# sema_2.net
KiCad netlist of a schematic drawn in Altium Designer
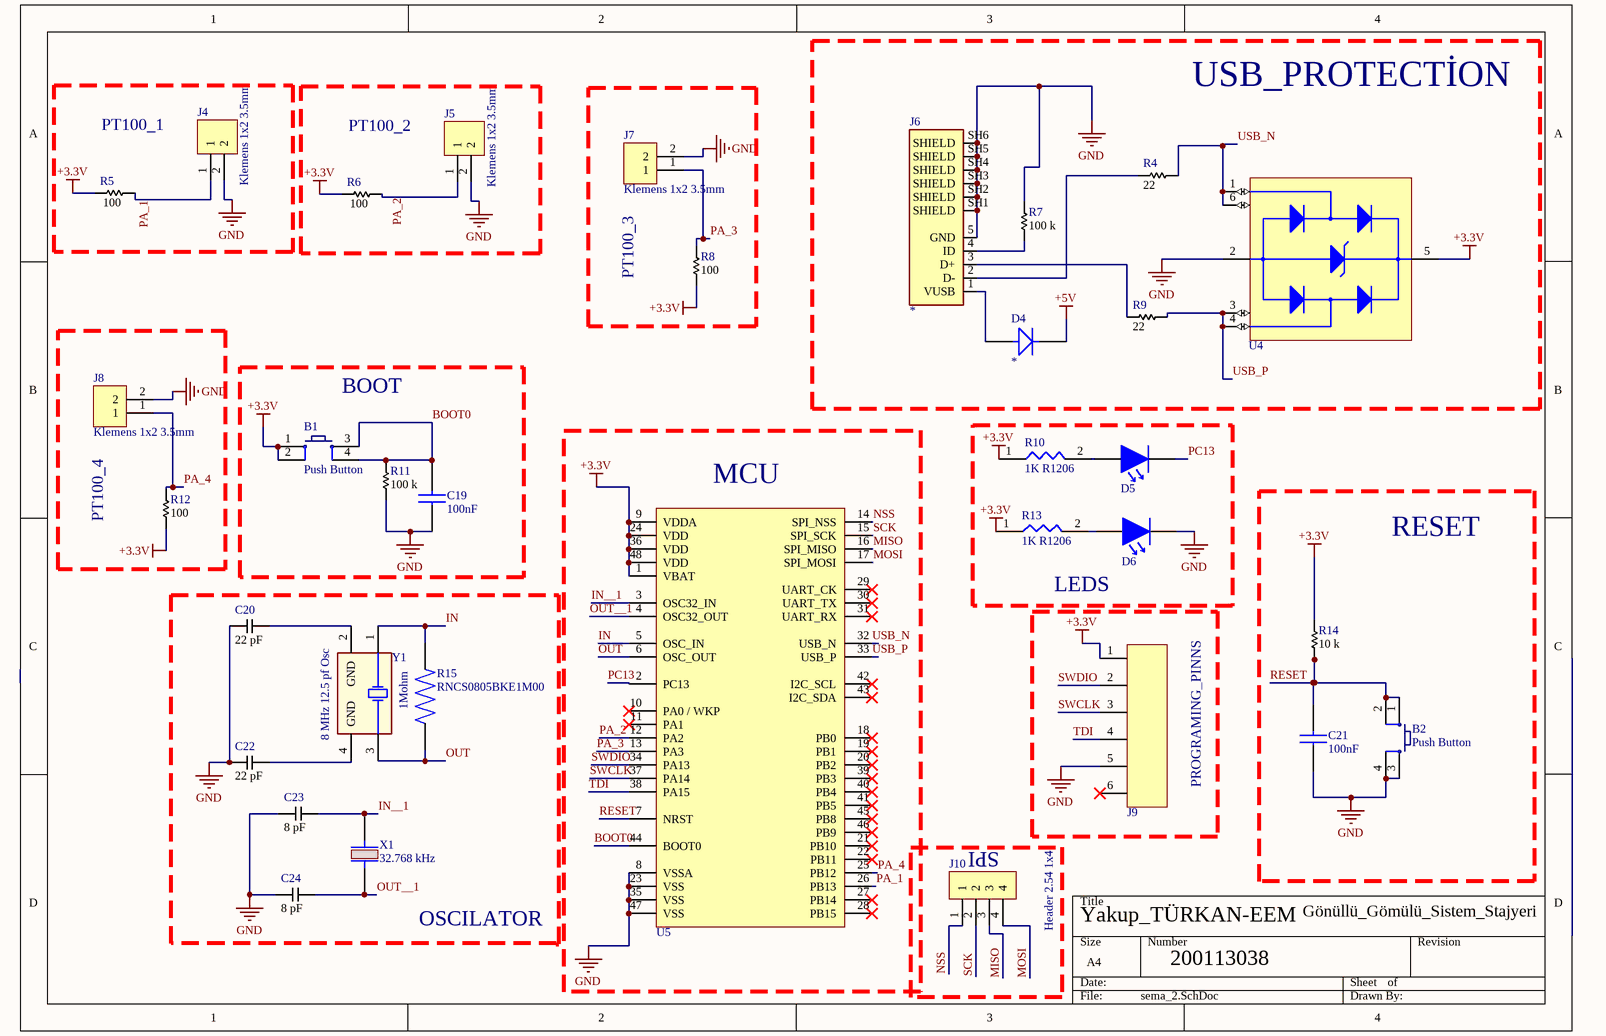
[diagram p0: sema_2.SchDoc]

(export (version "E")
  (design (tool "Eeschema 10.0.6"))
  (components
    (comp (ref "B1")
      (value "Push Button")
      (footprint "PUSB BUTTON-SMD")
      (description "Smd Push Button")
      (libsource (lib "YakupTrkn") (part "Push Button"))
    )
    (comp (ref "B2")
      (value "Push Button")
      (footprint "PUSB BUTTON-SMD")
      (description "Smd Push Button")
      (libsource (lib "YakupTrkn") (part "Push Button"))
    )
    (comp (ref "C19")
      (value "C0603C104K5RACTU")
      (footprint "CAP_0603")
      (description "CAP CER 100nF %10 0603 SMD")
      (fields
        (field (name "MANUFACTURER") "KEMET")
        (field (name "TOLERANCE") "10%")
        (field (name "CAPACITANCE") "100nF")
        (field (name "DESIGNED BY") "BERK")
      )
      (libsource (lib "YakupTrkn") (part "CAP CER 100nF 0603"))
    )
    (comp (ref "C20")
      (value "22pF")
      (footprint "SAMSUNG_CAP_0805_075")
      (description "CAP CER 27PF 50V C0G/NP0 0805")
      (fields (field (name "CAPACITANCE") "22 pF"))
      (libsource (lib "ilk") (part "22pF"))
    )
    (comp (ref "C21")
      (value "C0603C104K5RACTU")
      (footprint "CAP_0603")
      (description "CAP CER 100nF %10 0603 SMD")
      (fields
        (field (name "MANUFACTURER") "KEMET")
        (field (name "TOLERANCE") "10%")
        (field (name "CAPACITANCE") "100nF")
        (field (name "DESIGNED BY") "BERK")
      )
      (libsource (lib "YakupTrkn") (part "CAP CER 100nF 0603"))
    )
    (comp (ref "C22")
      (value "22pF")
      (footprint "SAMSUNG_CAP_0805_075")
      (description "CAP CER 27PF 50V C0G/NP0 0805")
      (fields (field (name "CAPACITANCE") "22 pF"))
      (libsource (lib "ilk") (part "22pF"))
    )
    (comp (ref "C23")
      (value "8pF")
      (footprint "SAMSUNG_CAP_0805_075")
      (description "CAP CER 1.2PF 50V C0G/NP0 0805")
      (fields (field (name "CAPACITANCE") "8 pF"))
      (libsource (lib "ilk") (part "8pF"))
    )
    (comp (ref "C24")
      (value "8pF")
      (footprint "SAMSUNG_CAP_0805_075")
      (description "CAP CER 1.2PF 50V C0G/NP0 0805")
      (fields (field (name "CAPACITANCE") "8 pF"))
      (libsource (lib "ilk") (part "8pF"))
    )
    (comp (ref "D4")
      (value "*")
      (footprint "MBRA210LT3G:DIOM5226X220N")
      (description "...employing the Schottky Barrier principle in a metal to silicon power rectifier.")
      (fields (field (name "MF") "{'manufacturer': u'ON Semiconductor'}") (field (name "MP") "MBRA210LT3G"))
      (libsource (lib "*") (part "MBRA210LT3G"))
    )
    (comp (ref "D5")
      (value "LTST-C171GKT")
      (footprint "LED_GREEN_0805")
      (description "Green 0805 130 º Min 5 mcd Typical 12 mcd Water Clear Lens SMT LED")
      (fields (field (name "MANUFACTURER") "Vishay Lite-On") (field (name "DESIGNED BY") "BERK"))
      (libsource (lib "ilk") (part "LED GREEN 0805"))
    )
    (comp (ref "D6")
      (value "LH R974-LP-1")
      (footprint "LED_RED_0805")
      (description "LED Uni-Color Hyper Red 660nm 2-Pin Chip 0805(2012Metric) T/R")
      (fields (field (name "MANUFACTURER") "Osram Opto") (field (name "DESIGNED BY") "BERK"))
      (libsource (lib "ilk") (part "LED RED 0805"))
    )
    (comp (ref "J4")
      (value "Klemens 1x2 3.5mm")
      (footprint "Klemens 1x2 - 3.5mm")
      (libsource (lib "") (part "Klemens 1x2 3.5mm_1"))
    )
    (comp (ref "J5")
      (value "Klemens 1x2 3.5mm")
      (footprint "Klemens 1x2 - 3.5mm")
      (libsource (lib "") (part "Klemens 1x2 3.5mm_1"))
    )
    (comp (ref "J6")
      (value "*")
      (footprint "10118192-0001LF:AMPHENOL_10118192-0001LF")
      (description "Single Port 5 Contact Horizontal Right Angle Shielded Micro B USB 2.0 Connector")
      (fields (field (name "MP") "10118192-0001LF") (field (name "MF") "{'manufacturer': u'FCI'}"))
      (libsource (lib "*") (part "10118192-0001LF"))
    )
    (comp (ref "J7")
      (value "Klemens 1x2 3.5mm")
      (footprint "Klemens 1x2 - 3.5mm")
      (libsource (lib "ilk") (part "Klemens 1x2 3.5mm"))
    )
    (comp (ref "J8")
      (value "Klemens 1x2 3.5mm")
      (footprint "Klemens 1x2 - 3.5mm")
      (libsource (lib "ilk") (part "Klemens 1x2 3.5mm"))
    )
    (comp (ref "J9")
      (value "64800611622")
      (footprint "64800611622")
      (description "1.50mm 6PIN Connector")
      (fields (field (name "MANUFACTURER") "Wurth Electronics"))
      (libsource (lib "*") (part "64800611622_conn_6pin"))
    )
    (comp (ref "J10")
      (value "Header 2.54 1x4")
      (footprint "Header 2.54 1x4")
      (libsource (lib "ilk") (part "Header 2.54 1x4"))
    )
    (comp (ref "R4")
      (value "0805W8J0220T5E")
      (footprint "ROYALOHM_RES_0805")
      (description "RES SMD 22 OHM 5% 1/8W 0805")
      (fields (field (name "RESISTANCE") "22"))
      (libsource (lib "YakupTrkn") (part "0805W8J0220T5E"))
    )
    (comp (ref "R5")
      (value "100ohm")
      (footprint "ROYALOHM_RES_0603")
      (description "RES SMD 100 OHM 5% 1/10W 0603")
      (fields (field (name "RESISTANCE") "100"))
      (libsource (lib "ilk") (part "100ohm"))
    )
    (comp (ref "R6")
      (value "100ohm")
      (footprint "ROYALOHM_RES_0603")
      (description "RES SMD 100 OHM 5% 1/10W 0603")
      (fields (field (name "RESISTANCE") "100"))
      (libsource (lib "ilk") (part "100ohm"))
    )
    (comp (ref "R7")
      (value "0603SAJ0104T5E")
      (footprint "ROYALOHM_RES_0603")
      (description "RES SMD 100K OHM 5% 1/10W 0603")
      (fields (field (name "RESISTANCE") "100 k"))
      (libsource (lib "YakupTrkn") (part "0603SAJ0104T5E"))
    )
    (comp (ref "R8")
      (value "100ohm")
      (footprint "ROYALOHM_RES_0603")
      (description "RES SMD 100 OHM 5% 1/10W 0603")
      (fields (field (name "RESISTANCE") "100"))
      (libsource (lib "ilk") (part "100ohm"))
    )
    (comp (ref "R9")
      (value "0805W8J0220T5E")
      (footprint "ROYALOHM_RES_0805")
      (description "RES SMD 22 OHM 5% 1/8W 0805")
      (fields (field (name "RESISTANCE") "22"))
      (libsource (lib "YakupTrkn") (part "0805W8J0220T5E"))
    )
    (comp (ref "R10")
      (value "1K R1206")
      (footprint "R1206 Resıstor")
      (libsource (lib "ilk") (part "1K R1206"))
    )
    (comp (ref "R11")
      (value "0805S8J0104T5E")
      (footprint "ROYALOHM_RES_0805")
      (description "RES SMD 100K OHM 5% 1/8W 0805")
      (fields (field (name "RESISTANCE") "100 k"))
      (libsource (lib "ilk") (part "0805S8J0104T5E"))
    )
    (comp (ref "R12")
      (value "100ohm")
      (footprint "ROYALOHM_RES_0603")
      (description "RES SMD 100 OHM 5% 1/10W 0603")
      (fields (field (name "RESISTANCE") "100"))
      (libsource (lib "ilk") (part "100ohm"))
    )
    (comp (ref "R13")
      (value "1K R1206")
      (footprint "R1206 Resıstor")
      (libsource (lib "ilk") (part "1K R1206"))
    )
    (comp (ref "R14")
      (value "10k")
      (footprint "ROYALOHM_RES_0805")
      (description "RES SMD 10K OHM 1% 1/8W 0805")
      (fields (field (name "RESISTANCE") "10 k"))
      (libsource (lib "ilk") (part "10k"))
    )
    (comp (ref "R15")
      (value "RNCS0805BKE1M00")
      (footprint "RNCS0805BKE1M00:RESC2012X65N")
      (fields (field (name "MF") "{'manufacturer': u'Stackpole Electronics Inc'}"))
      (libsource (lib "ilk") (part "RNCS0805BKE1M00"))
    )
    (comp (ref "U4")
      (value "USBLC6-2SC6")
      (footprint "SOT23-6L")
      (description "TVS DIODE 5.25V 17V SOT23-6")
      (fields (field (name "MANUFACTURER") "STMicroelectronics") (field (name "DESIGNED BY") "BERK"))
      (libsource (lib "YakupTrkn") (part "USB PROTECTION"))
    )
    (comp (ref "U5")
      (value "STM32F103C6T6A")
      (footprint "LQFP-48")
      (description "MCU 32-bit STM32F ARM Cortex M3 RISC 32KB Flash 2.5V/3.3V 48-Pin LQFP Tray")
      (fields (field (name "MANUFACTURER") "STMicroelectronics") (field (name "DESIGNED BY") "BERK"))
      (libsource (lib "ilk") (part "STM32F103C6T6A"))
    )
    (comp (ref "X1")
      (value "ABS05-32.768KHZ-T")
      (footprint "ABS05")
      (description "Crystal, 32.768 kHz, SMD, 1.6mm x 1mm, 12.5 pF, 20 ppm, ABS05 Series")
      (fields
        (field (name "MANUFACTURER") "Abracon")
        (field (name "TOLERANCE") "20ppm")
        (field (name "OPERATING FREQUENCY") "32.768 kHz")
        (field (name "DESIGNED BY") "BERK")
      )
      (libsource (lib "ilk") (part "CRYSTAL 32768kHZ"))
    )
    (comp (ref "Y1")
      (value "8 MHz 12.5 pf Osc")
      (footprint "8 MHZ Osc.")
      (libsource (lib "ilk") (part "8 MHz 12.5 pf Osc"))
    )
  )
  (nets
    (net (code "1") (name "+3.3V") (class "Default")
      (node (ref "B1") (pin "1") (pinfunction "1_1") (pintype "passive"))
      (node (ref "B1") (pin "2") (pinfunction "2_2") (pintype "passive"))
      (node (ref "J9") (pin "1") (pintype "power_in"))
      (node (ref "R10") (pin "1") (pinfunction "1_1") (pintype "passive"))
      (node (ref "R12") (pin "1") (pinfunction "1_1") (pintype "passive"))
      (node (ref "R13") (pin "1") (pinfunction "1_1") (pintype "passive"))
      (node (ref "R14") (pin "2") (pinfunction "2_2") (pintype "passive"))
      (node (ref "R5") (pin "1") (pinfunction "1_1") (pintype "passive"))
      (node (ref "R6") (pin "1") (pinfunction "1_1") (pintype "passive"))
      (node (ref "R8") (pin "1") (pinfunction "1_1") (pintype "passive"))
      (node (ref "U4") (pin "5") (pinfunction "VBUS_5") (pintype "power_in"))
      (node (ref "U5") (pin "1") (pinfunction "VBAT_1") (pintype "passive"))
      (node (ref "U5") (pin "24") (pinfunction "VDD_24") (pintype "passive"))
      (node (ref "U5") (pin "36") (pinfunction "VDD_36") (pintype "passive"))
      (node (ref "U5") (pin "48") (pinfunction "VDD_48") (pintype "passive"))
      (node (ref "U5") (pin "9") (pinfunction "VDDA_9") (pintype "passive"))
    )
    (net (code "2") (name "+5V") (class "Default")
      (node (ref "D4") (pin "1") (pinfunction "K_1") (pintype "passive"))
    )
    (net (code "3") (name "/BOOT0") (class "Default")
      (node (ref "B1") (pin "3") (pinfunction "3_3") (pintype "passive"))
      (node (ref "B1") (pin "4") (pinfunction "4_4") (pintype "passive"))
      (node (ref "C19") (pin "2") (pinfunction "2_2") (pintype "passive"))
      (node (ref "R11") (pin "2") (pinfunction "2_2") (pintype "passive"))
      (node (ref "U5") (pin "44") (pinfunction "BOOT0_44") (pintype "passive"))
    )
    (net (code "4") (name "/IN") (class "Default")
      (node (ref "R15") (pin "2") (pinfunction "2_2") (pintype "passive"))
      (node (ref "U5") (pin "5") (pinfunction "OSC_IN_5") (pintype "passive"))
      (node (ref "Y1") (pin "1") (pintype "power_in"))
    )
    (net (code "5") (name "/IN__1") (class "Default")
      (node (ref "C23") (pin "2") (pinfunction "2_2") (pintype "passive"))
      (node (ref "U5") (pin "3") (pinfunction "OSC32_IN_3") (pintype "passive"))
      (node (ref "X1") (pin "2") (pinfunction "2_2") (pintype "passive"))
    )
    (net (code "6") (name "/MISO") (class "Default")
      (node (ref "J10") (pin "3") (pinfunction "3_3") (pintype "passive"))
      (node (ref "U5") (pin "16") (pinfunction "SPI_MISO_16") (pintype "passive"))
    )
    (net (code "7") (name "/MOSI") (class "Default")
      (node (ref "J10") (pin "4") (pinfunction "4_4") (pintype "passive"))
      (node (ref "U5") (pin "17") (pinfunction "SPI_MOSI_17") (pintype "passive"))
    )
    (net (code "8") (name "/NSS") (class "Default")
      (node (ref "J10") (pin "1") (pinfunction "1_1") (pintype "passive"))
      (node (ref "U5") (pin "14") (pinfunction "SPI_NSS_14") (pintype "passive"))
    )
    (net (code "9") (name "/OUT") (class "Default")
      (node (ref "R15") (pin "1") (pinfunction "1_1") (pintype "passive"))
      (node (ref "U5") (pin "6") (pinfunction "OSC_OUT_6") (pintype "passive"))
      (node (ref "Y1") (pin "3") (pintype "passive"))
    )
    (net (code "10") (name "/OUT__1") (class "Default")
      (node (ref "C24") (pin "2") (pinfunction "2_2") (pintype "passive"))
      (node (ref "U5") (pin "4") (pinfunction "OSC32_OUT_4") (pintype "passive"))
      (node (ref "X1") (pin "1") (pinfunction "1_1") (pintype "passive"))
    )
    (net (code "11") (name "/PA_1") (class "Default")
      (node (ref "J4") (pin "1") (pinfunction "1_1") (pintype "passive"))
      (node (ref "R5") (pin "2") (pinfunction "2_2") (pintype "passive"))
      (node (ref "U5") (pin "26") (pinfunction "PB13_26") (pintype "passive"))
    )
    (net (code "12") (name "/PA_2") (class "Default")
      (node (ref "J5") (pin "1") (pinfunction "1_1") (pintype "passive"))
      (node (ref "R6") (pin "2") (pinfunction "2_2") (pintype "passive"))
      (node (ref "U5") (pin "12") (pinfunction "PA2_12") (pintype "passive"))
    )
    (net (code "13") (name "/PA_3") (class "Default")
      (node (ref "J7") (pin "1") (pinfunction "1_1") (pintype "passive"))
      (node (ref "R8") (pin "2") (pinfunction "2_2") (pintype "passive"))
      (node (ref "U5") (pin "13") (pinfunction "PA3_13") (pintype "passive"))
    )
    (net (code "14") (name "/PA_4") (class "Default")
      (node (ref "J8") (pin "1") (pinfunction "1_1") (pintype "passive"))
      (node (ref "R12") (pin "2") (pinfunction "2_2") (pintype "passive"))
      (node (ref "U5") (pin "25") (pinfunction "PB12_25") (pintype "passive"))
    )
    (net (code "15") (name "/PC13") (class "Default")
      (node (ref "D5") (pin "1") (pinfunction "1_1") (pintype "power_in"))
      (node (ref "U5") (pin "2") (pinfunction "PC13_2") (pintype "passive"))
    )
    (net (code "16") (name "/RESET") (class "Default")
      (node (ref "B2") (pin "1") (pinfunction "1_1") (pintype "passive"))
      (node (ref "B2") (pin "2") (pinfunction "2_2") (pintype "passive"))
      (node (ref "C21") (pin "2") (pinfunction "2_2") (pintype "passive"))
      (node (ref "R14") (pin "1") (pinfunction "1_1") (pintype "passive"))
      (node (ref "U5") (pin "7") (pinfunction "NRST_7") (pintype "passive"))
    )
    (net (code "17") (name "/SCK") (class "Default")
      (node (ref "J10") (pin "2") (pinfunction "2_2") (pintype "passive"))
      (node (ref "U5") (pin "15") (pinfunction "SPI_SCK_15") (pintype "passive"))
    )
    (net (code "18") (name "/SWCLK") (class "Default")
      (node (ref "J9") (pin "3") (pintype "power_in"))
      (node (ref "U5") (pin "37") (pinfunction "PA14_37") (pintype "passive"))
    )
    (net (code "19") (name "/SWDIO") (class "Default")
      (node (ref "J9") (pin "2") (pintype "power_in"))
      (node (ref "U5") (pin "34") (pinfunction "PA13_34") (pintype "passive"))
    )
    (net (code "20") (name "/TDI") (class "Default")
      (node (ref "J9") (pin "4") (pintype "power_in"))
      (node (ref "U5") (pin "38") (pinfunction "PA15_38") (pintype "passive"))
    )
    (net (code "21") (name "/USB_N") (class "Default")
      (node (ref "R4") (pin "2") (pinfunction "2_2") (pintype "passive"))
      (node (ref "U4") (pin "1") (pinfunction "I/O1_1") (pintype "bidirectional"))
      (node (ref "U4") (pin "6") (pinfunction "I/O1_6") (pintype "bidirectional"))
      (node (ref "U5") (pin "32") (pinfunction "USB_N_32") (pintype "passive"))
    )
    (net (code "22") (name "/USB_P") (class "Default")
      (node (ref "R9") (pin "2") (pinfunction "2_2") (pintype "passive"))
      (node (ref "U4") (pin "3") (pinfunction "I/O2_3") (pintype "bidirectional"))
      (node (ref "U4") (pin "4") (pinfunction "I/O2_4") (pintype "bidirectional"))
      (node (ref "U5") (pin "33") (pinfunction "USB_P_33") (pintype "passive"))
    )
    (net (code "23") (name "GND") (class "Default")
      (node (ref "B2") (pin "3") (pinfunction "3_3") (pintype "passive"))
      (node (ref "B2") (pin "4") (pinfunction "4_4") (pintype "passive"))
      (node (ref "C19") (pin "1") (pinfunction "1_1") (pintype "passive"))
      (node (ref "C20") (pin "1") (pinfunction "1_1") (pintype "passive"))
      (node (ref "C21") (pin "1") (pinfunction "1_1") (pintype "passive"))
      (node (ref "C22") (pin "1") (pinfunction "1_1") (pintype "passive"))
      (node (ref "C23") (pin "1") (pinfunction "1_1") (pintype "passive"))
      (node (ref "C24") (pin "1") (pinfunction "1_1") (pintype "passive"))
      (node (ref "D6") (pin "1") (pinfunction "1_1") (pintype "power_in"))
      (node (ref "J4") (pin "2") (pinfunction "2_2") (pintype "passive"))
      (node (ref "J5") (pin "2") (pinfunction "2_2") (pintype "passive"))
      (node (ref "J6") (pin "5") (pinfunction "GND_5") (pintype "passive"))
      (node (ref "J6") (pin "SH1") (pinfunction "SHIELD_SH1") (pintype "passive"))
      (node (ref "J6") (pin "SH2") (pinfunction "SHIELD_SH2") (pintype "passive"))
      (node (ref "J6") (pin "SH3") (pinfunction "SHIELD_SH3") (pintype "passive"))
      (node (ref "J6") (pin "SH4") (pinfunction "SHIELD_SH4") (pintype "passive"))
      (node (ref "J6") (pin "SH5") (pinfunction "SHIELD_SH5") (pintype "passive"))
      (node (ref "J6") (pin "SH6") (pinfunction "SHIELD_SH6") (pintype "passive"))
      (node (ref "J7") (pin "2") (pinfunction "2_2") (pintype "passive"))
      (node (ref "J8") (pin "2") (pinfunction "2_2") (pintype "passive"))
      (node (ref "J9") (pin "5") (pintype "power_in"))
      (node (ref "R11") (pin "1") (pinfunction "1_1") (pintype "passive"))
      (node (ref "R7") (pin "2") (pinfunction "2_2") (pintype "passive"))
      (node (ref "U4") (pin "2") (pinfunction "GND_2") (pintype "power_in"))
      (node (ref "U5") (pin "23") (pinfunction "VSS_23") (pintype "passive"))
      (node (ref "U5") (pin "35") (pinfunction "VSS_35") (pintype "passive"))
      (node (ref "U5") (pin "47") (pinfunction "VSS_47") (pintype "passive"))
      (node (ref "U5") (pin "8") (pinfunction "VSSA_8") (pintype "passive"))
    )
    (net (code "24") (name "Net-(C20-Pad2)") (class "Default")
      (node (ref "C20") (pin "2") (pinfunction "2_2") (pintype "passive"))
      (node (ref "Y1") (pin "2") (pinfunction "GND_2") (pintype "power_in"))
    )
    (net (code "25") (name "Net-(C22-Pad2)") (class "Default")
      (node (ref "C22") (pin "2") (pinfunction "2_2") (pintype "passive"))
      (node (ref "Y1") (pin "4") (pinfunction "GND_4") (pintype "passive"))
    )
    (net (code "26") (name "Net-(D4-A)") (class "Default")
      (node (ref "D4") (pin "2") (pinfunction "A_2") (pintype "passive"))
      (node (ref "J6") (pin "1") (pinfunction "VUSB_1") (pintype "passive"))
    )
    (net (code "27") (name "Net-(D5-Pad2)") (class "Default")
      (node (ref "D5") (pin "2") (pinfunction "2_2") (pintype "power_in"))
      (node (ref "R10") (pin "2") (pinfunction "2_2") (pintype "passive"))
    )
    (net (code "28") (name "Net-(D6-Pad2)") (class "Default")
      (node (ref "D6") (pin "2") (pinfunction "2_2") (pintype "power_in"))
      (node (ref "R13") (pin "2") (pinfunction "2_2") (pintype "passive"))
    )
    (net (code "29") (name "Net-(J6-D+)") (class "Default")
      (node (ref "J6") (pin "3") (pinfunction "D+_3") (pintype "passive"))
      (node (ref "R9") (pin "1") (pinfunction "1_1") (pintype "passive"))
    )
    (net (code "30") (name "Net-(J6-D-)") (class "Default")
      (node (ref "J6") (pin "2") (pinfunction "D-_2") (pintype "passive"))
      (node (ref "R4") (pin "1") (pinfunction "1_1") (pintype "passive"))
    )
    (net (code "31") (name "Net-(J6-ID)") (class "Default")
      (node (ref "J6") (pin "4") (pinfunction "ID_4") (pintype "passive"))
      (node (ref "R7") (pin "1") (pinfunction "1_1") (pintype "passive"))
    )
    (net (code "32") (name "unconnected-(J9-Pad6)") (class "Default")
      (node (ref "J9") (pin "6") (pintype "power_in+no_connect"))
    )
    (net (code "33") (name "unconnected-(U5-I2C_SCL-Pad42)") (class "Default")
      (node (ref "U5") (pin "42") (pinfunction "I2C_SCL_42") (pintype "passive+no_connect"))
    )
    (net (code "34") (name "unconnected-(U5-I2C_SDA-Pad43)") (class "Default")
      (node (ref "U5") (pin "43") (pinfunction "I2C_SDA_43") (pintype "passive+no_connect"))
    )
    (net (code "35") (name "unconnected-(U5-PA0_{slash}_WKP-Pad10)") (class "Default")
      (node (ref "U5") (pin "10") (pinfunction "PA0_/_WKP_10") (pintype "passive+no_connect"))
    )
    (net (code "36") (name "unconnected-(U5-PA1-Pad11)") (class "Default")
      (node (ref "U5") (pin "11") (pinfunction "PA1_11") (pintype "passive+no_connect"))
    )
    (net (code "37") (name "unconnected-(U5-PB0-Pad18)") (class "Default")
      (node (ref "U5") (pin "18") (pinfunction "PB0_18") (pintype "passive+no_connect"))
    )
    (net (code "38") (name "unconnected-(U5-PB1-Pad19)") (class "Default")
      (node (ref "U5") (pin "19") (pinfunction "PB1_19") (pintype "passive+no_connect"))
    )
    (net (code "39") (name "unconnected-(U5-PB2-Pad20)") (class "Default")
      (node (ref "U5") (pin "20") (pinfunction "PB2_20") (pintype "passive+no_connect"))
    )
    (net (code "40") (name "unconnected-(U5-PB3-Pad39)") (class "Default")
      (node (ref "U5") (pin "39") (pinfunction "PB3_39") (pintype "passive+no_connect"))
    )
    (net (code "41") (name "unconnected-(U5-PB4-Pad40)") (class "Default")
      (node (ref "U5") (pin "40") (pinfunction "PB4_40") (pintype "passive+no_connect"))
    )
    (net (code "42") (name "unconnected-(U5-PB5-Pad41)") (class "Default")
      (node (ref "U5") (pin "41") (pinfunction "PB5_41") (pintype "passive+no_connect"))
    )
    (net (code "43") (name "unconnected-(U5-PB8-Pad45)") (class "Default")
      (node (ref "U5") (pin "45") (pinfunction "PB8_45") (pintype "passive+no_connect"))
    )
    (net (code "44") (name "unconnected-(U5-PB9-Pad46)") (class "Default")
      (node (ref "U5") (pin "46") (pinfunction "PB9_46") (pintype "passive+no_connect"))
    )
    (net (code "45") (name "unconnected-(U5-PB10-Pad21)") (class "Default")
      (node (ref "U5") (pin "21") (pinfunction "PB10_21") (pintype "passive+no_connect"))
    )
    (net (code "46") (name "unconnected-(U5-PB11-Pad22)") (class "Default")
      (node (ref "U5") (pin "22") (pinfunction "PB11_22") (pintype "passive+no_connect"))
    )
    (net (code "47") (name "unconnected-(U5-PB14-Pad27)") (class "Default")
      (node (ref "U5") (pin "27") (pinfunction "PB14_27") (pintype "passive+no_connect"))
    )
    (net (code "48") (name "unconnected-(U5-PB15-Pad28)") (class "Default")
      (node (ref "U5") (pin "28") (pinfunction "PB15_28") (pintype "passive+no_connect"))
    )
    (net (code "49") (name "unconnected-(U5-UART_CK-Pad29)") (class "Default")
      (node (ref "U5") (pin "29") (pinfunction "UART_CK_29") (pintype "passive+no_connect"))
    )
    (net (code "50") (name "unconnected-(U5-UART_RX-Pad31)") (class "Default")
      (node (ref "U5") (pin "31") (pinfunction "UART_RX_31") (pintype "passive+no_connect"))
    )
    (net (code "51") (name "unconnected-(U5-UART_TX-Pad30)") (class "Default")
      (node (ref "U5") (pin "30") (pinfunction "UART_TX_30") (pintype "passive+no_connect"))
    )
  )
)
